# Sheet_TX.net
KiCad netlist of a schematic drawn in Altium Designer
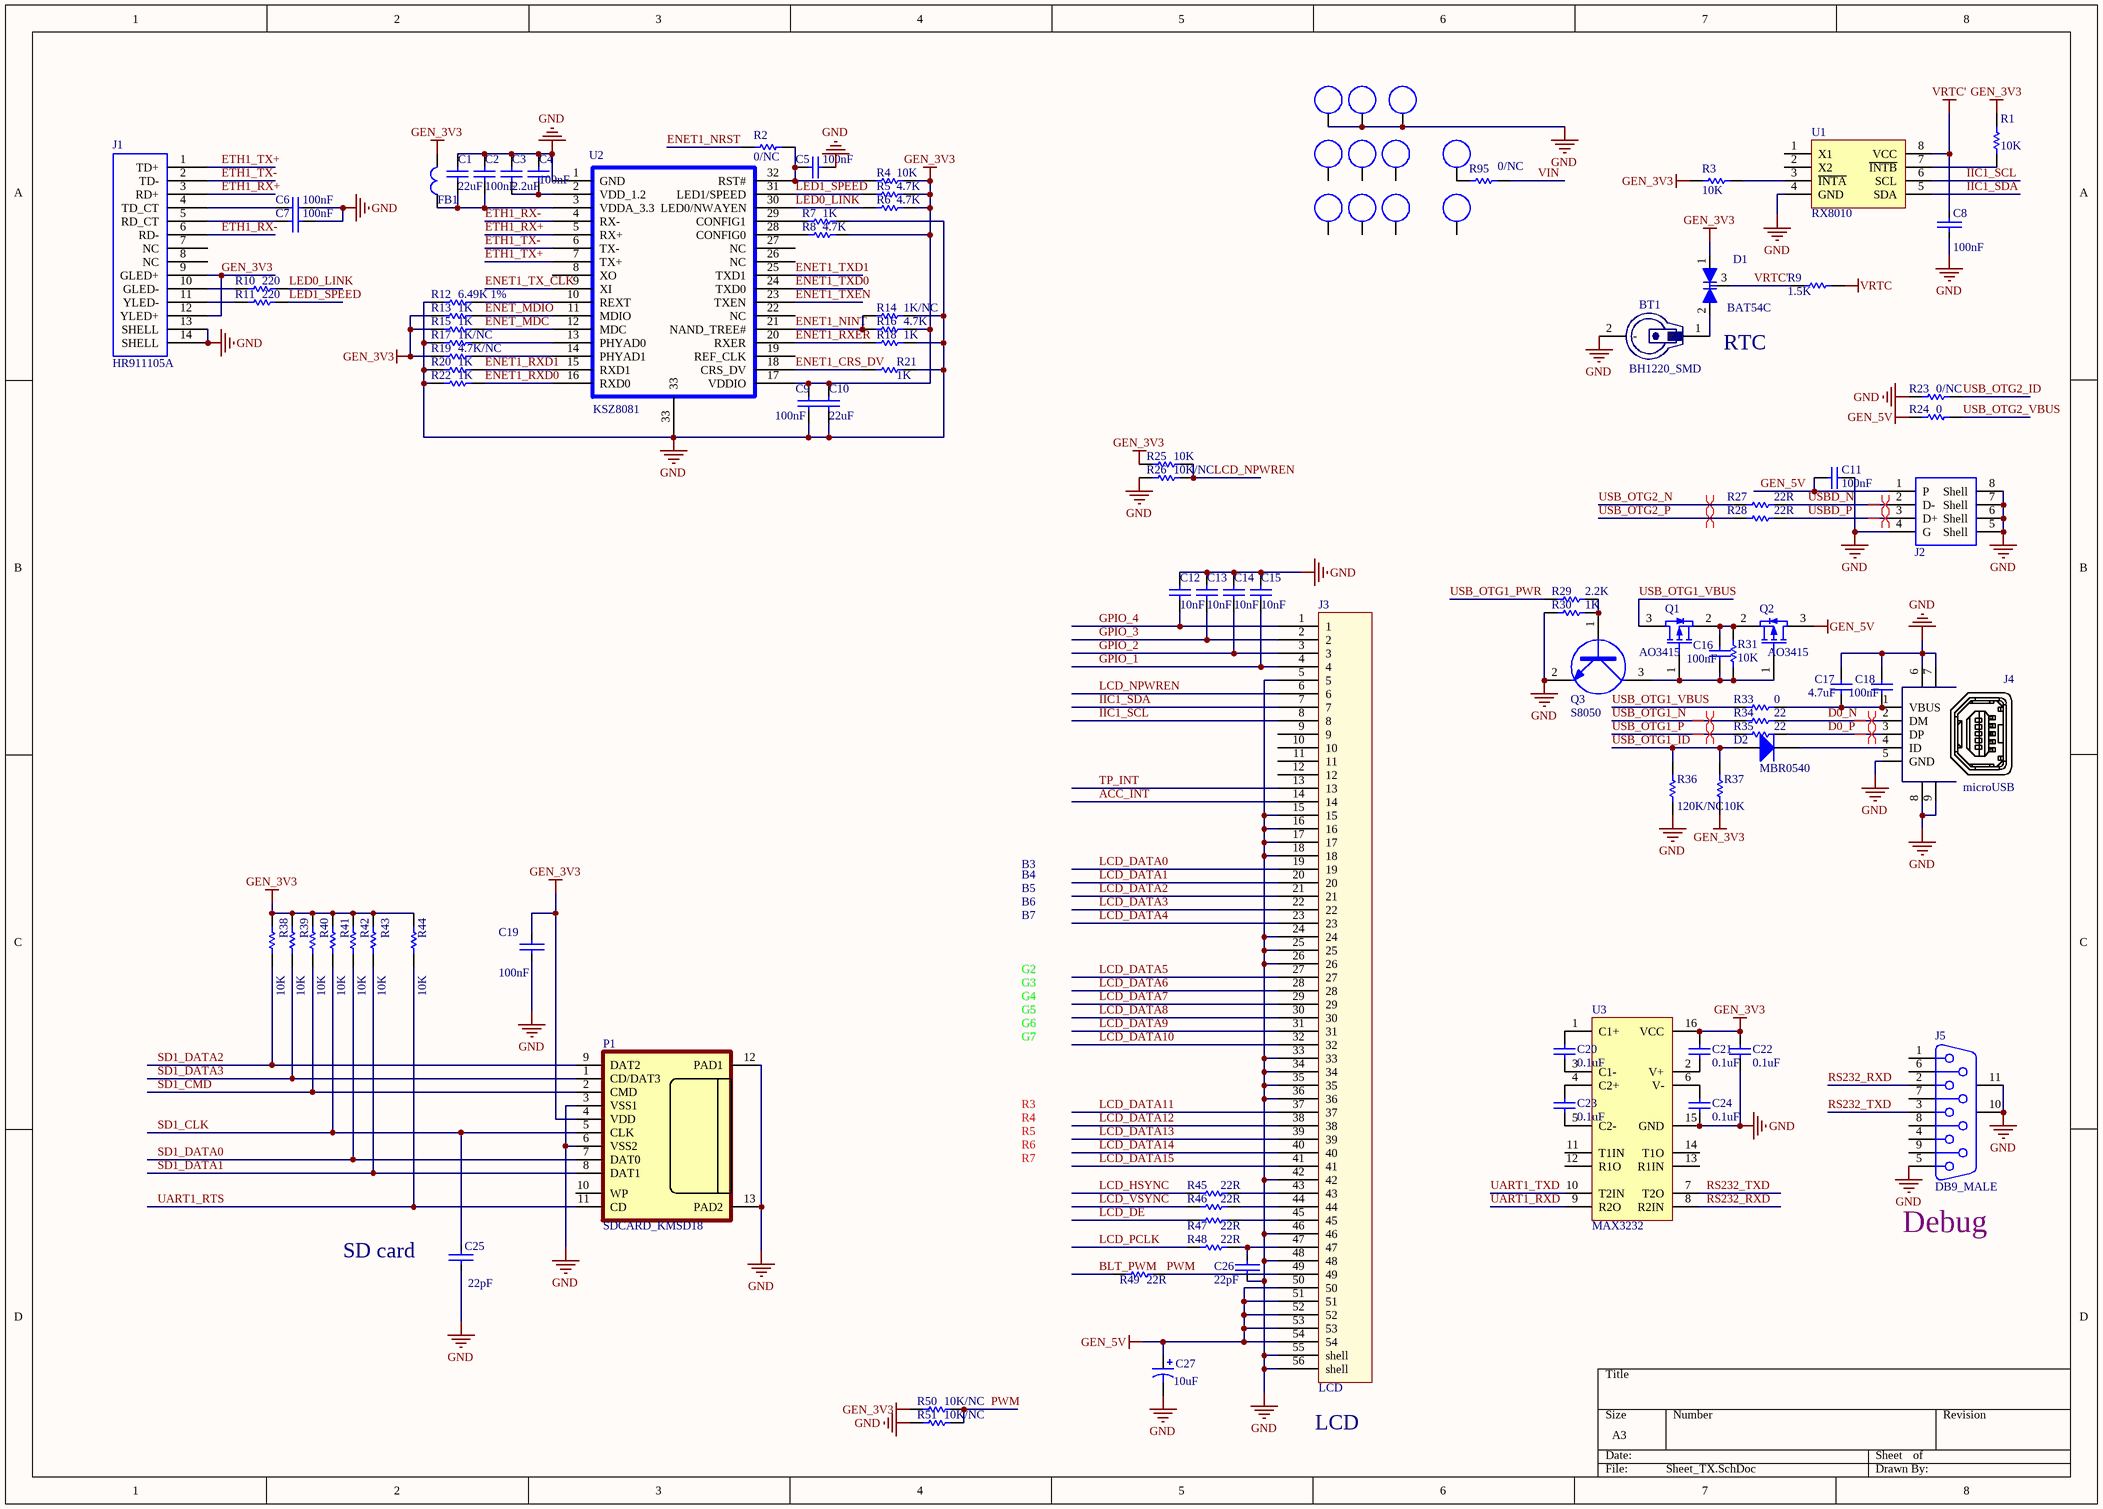
[diagram p0: Sheet_TX.SchDoc]

(export (version "E")
  (design (tool "Eeschema 10.0.6"))
  (components
    (comp (ref "BT1")
      (value "BH1220_SMD")
      (footprint "B1220")
      (libsource (lib "AM335X_bottom") (part "Battery"))
    )
    (comp (ref "C1")
      (value "22uF")
      (footprint "0603")
      (description "Capacitor")
      (fields (field (name "Comment") "Cap") (field (name "PUBLISHER") "Altium Limited"))
      (libsource (lib "Miscellaneous Devices") (part "Cap"))
    )
    (comp (ref "C2")
      (value "100nF")
      (footprint "0603")
      (description "Capacitor")
      (fields (field (name "Comment") "Cap") (field (name "PUBLISHER") "Altium Limited"))
      (libsource (lib "Miscellaneous Devices") (part "Cap"))
    )
    (comp (ref "C3")
      (value "2.2uF")
      (footprint "0603")
      (description "Capacitor")
      (fields (field (name "Comment") "Cap") (field (name "PUBLISHER") "Altium Limited"))
      (libsource (lib "Miscellaneous Devices") (part "Cap"))
    )
    (comp (ref "C4")
      (value "100nF")
      (footprint "0603")
      (description "Capacitor")
      (fields (field (name "Comment") "Cap") (field (name "PUBLISHER") "Altium Limited"))
      (libsource (lib "Miscellaneous Devices") (part "Cap"))
    )
    (comp (ref "C5")
      (value "100nF")
      (footprint "0603")
      (description "Capacitor")
      (fields (field (name "Comment") "Cap") (field (name "PUBLISHER") "Altium Limited"))
      (libsource (lib "Miscellaneous Devices") (part "Cap"))
    )
    (comp (ref "C6")
      (value "100nF")
      (footprint "0603")
      (description "Capacitor")
      (fields (field (name "Comment") "Cap") (field (name "PUBLISHER") "Altium Limited"))
      (libsource (lib "Miscellaneous Devices") (part "Cap"))
    )
    (comp (ref "C7")
      (value "100nF")
      (footprint "0603")
      (description "Capacitor")
      (fields (field (name "Comment") "Cap") (field (name "PUBLISHER") "Altium Limited"))
      (libsource (lib "Miscellaneous Devices") (part "Cap"))
    )
    (comp (ref "C8")
      (value "100nF")
      (footprint "0603")
      (libsource (lib "SMARTCORTEX M3-1700_1") (part "CAP_1"))
    )
    (comp (ref "C9")
      (value "100nF")
      (footprint "0603")
      (description "Capacitor")
      (fields (field (name "Comment") "Cap") (field (name "PUBLISHER") "Altium Limited"))
      (libsource (lib "Miscellaneous Devices") (part "Cap"))
    )
    (comp (ref "C10")
      (value "22uF")
      (footprint "0603")
      (description "Capacitor")
      (fields (field (name "Comment") "Cap") (field (name "PUBLISHER") "Altium Limited"))
      (libsource (lib "Miscellaneous Devices") (part "Cap"))
    )
    (comp (ref "C11")
      (value "100nF")
      (footprint "0603")
      (description "Capacitor (Semiconductor SIM Model)")
      (fields (field (name "Comment") "C0603") (field (name "PUBLISHER") "Altium Limited"))
      (libsource (lib "Miscellaneous Devices") (part "Cap Semi"))
    )
    (comp (ref "C12")
      (value "10nF")
      (footprint "0603")
      (description "Capacitor (Semiconductor SIM Model)")
      (fields (field (name "Comment") "C0603") (field (name "PUBLISHER") "Altium Limited"))
      (libsource (lib "Miscellaneous Devices") (part "Cap Semi"))
    )
    (comp (ref "C13")
      (value "10nF")
      (footprint "0603")
      (description "Capacitor (Semiconductor SIM Model)")
      (fields (field (name "Comment") "C0603") (field (name "PUBLISHER") "Altium Limited"))
      (libsource (lib "Miscellaneous Devices") (part "Cap Semi"))
    )
    (comp (ref "C14")
      (value "10nF")
      (footprint "0603")
      (description "Capacitor (Semiconductor SIM Model)")
      (fields (field (name "Comment") "C0603") (field (name "PUBLISHER") "Altium Limited"))
      (libsource (lib "Miscellaneous Devices") (part "Cap Semi"))
    )
    (comp (ref "C15")
      (value "10nF")
      (footprint "0603")
      (description "Capacitor (Semiconductor SIM Model)")
      (fields (field (name "Comment") "C0603") (field (name "PUBLISHER") "Altium Limited"))
      (libsource (lib "Miscellaneous Devices") (part "Cap Semi"))
    )
    (comp (ref "C16")
      (value "100nF")
      (footprint "0603")
      (description "Capacitor (Semiconductor SIM Model)")
      (fields (field (name "Comment") "C0603") (field (name "PUBLISHER") "Altium Limited"))
      (libsource (lib "Miscellaneous Devices") (part "Cap Semi"))
    )
    (comp (ref "C17")
      (value "4.7uF")
      (footprint "0603")
      (description "Capacitor (Semiconductor SIM Model)")
      (fields (field (name "Comment") "C0603") (field (name "PUBLISHER") "Altium Limited"))
      (libsource (lib "Miscellaneous Devices") (part "Cap Semi"))
    )
    (comp (ref "C18")
      (value "100nF")
      (footprint "0603")
      (description "Capacitor (Semiconductor SIM Model)")
      (fields (field (name "Comment") "C0603") (field (name "PUBLISHER") "Altium Limited"))
      (libsource (lib "Miscellaneous Devices") (part "Cap Semi"))
    )
    (comp (ref "C19")
      (value "100nF")
      (footprint "0603")
      (libsource (lib "SMARTCORTEX M3-1700_1") (part "CAP_1"))
    )
    (comp (ref "C20")
      (value "0.1uF")
      (footprint "0603")
      (description "Capacitor")
      (fields (field (name "Comment") "C0603") (field (name "PUBLISHER") "Altium Limited"))
      (libsource (lib "Miscellaneous Devices") (part "Cap"))
    )
    (comp (ref "C21")
      (value "0.1uF")
      (footprint "0603")
      (description "Capacitor")
      (fields (field (name "Comment") "C0603") (field (name "PUBLISHER") "Altium Limited"))
      (libsource (lib "Miscellaneous Devices") (part "Cap"))
    )
    (comp (ref "C22")
      (value "0.1uF")
      (footprint "0603")
      (description "Capacitor")
      (fields (field (name "Comment") "C0603") (field (name "PUBLISHER") "Altium Limited"))
      (libsource (lib "Miscellaneous Devices") (part "Cap"))
    )
    (comp (ref "C23")
      (value "0.1uF")
      (footprint "0603")
      (description "Capacitor")
      (fields (field (name "Comment") "C0603") (field (name "PUBLISHER") "Altium Limited"))
      (libsource (lib "Miscellaneous Devices") (part "Cap"))
    )
    (comp (ref "C24")
      (value "0.1uF")
      (footprint "0603")
      (description "Capacitor")
      (fields (field (name "Comment") "C0603") (field (name "PUBLISHER") "Altium Limited"))
      (libsource (lib "Miscellaneous Devices") (part "Cap"))
    )
    (comp (ref "C25")
      (value "22pF")
      (footprint "0603")
      (libsource (lib "SMARTCORTEX M3-1700_1") (part "CAP_1"))
    )
    (comp (ref "C26")
      (value "22pF")
      (footprint "0603")
      (libsource (lib "SMARTCORTEX M3-1700_1") (part "CAP_1"))
    )
    (comp (ref "C27")
      (value "10uF")
      (footprint "3216A")
      (description "Polarized Capacitor (Radial)")
      (fields (field (name "Comment") "Cap Pol1") (field (name "PUBLISHER") "Altium Limited"))
      (libsource (lib "Miscellaneous Devices") (part "Cap Pol1"))
    )
    (comp (ref "D1")
      (value "BAT54C")
      (footprint "SOT23")
      (description "SOT23-3_D")
      (libsource (lib "S5PV210_core") (part "BAT54C"))
    )
    (comp (ref "D2")
      (value "MBR0540")
      (footprint "SOD-123")
      (description "Default Diode")
      (fields (field (name "PUBLISHER") "Altium Limited"))
      (libsource (lib "Miscellaneous Devices") (part "Diode"))
    )
    (comp (ref "FB1")
      (value "CZ")
      (footprint "0603")
      (description "Inductor")
      (fields (field (name "PUBLISHER") "Altium Limited"))
      (libsource (lib "Schlib_UL") (part "CZ"))
    )
    (comp (ref "H1") (value "hole") (footprint "HOLE") (libsource (lib "arm_SL") (part "hole")))
    (comp (ref "H2") (value "hole") (footprint "HOLE") (libsource (lib "arm_SL") (part "hole")))
    (comp (ref "H3") (value "hole") (footprint "HOLE") (libsource (lib "arm_SL") (part "hole")))
    (comp (ref "H4") (value "hole") (footprint "HOLE") (libsource (lib "arm_SL") (part "hole")))
    (comp (ref "H7") (value "hole") (footprint "FLQRS") (libsource (lib "arm_SL") (part "hole")))
    (comp (ref "J1")
      (value "HR911105A")
      (footprint "RJ-45A12")
      (libsource (lib "Schlib_UL") (part "HR911105A"))
    )
    (comp (ref "J2") (value "USB-A-F-W") (footprint "USB-C") (libsource (lib "Schlib_YX") (part "USB-A-F-W")))
    (comp (ref "J3") (value "LCD") (footprint "FPC54_A") (libsource (lib "OK6410_LIB") (part "FPC54")))
    (comp (ref "J4")
      (value "microUSB")
      (footprint "MICRO_USB")
      (libsource (lib "AM335X_bottom") (part "miniUSB"))
    )
    (comp (ref "J5")
      (value "DB9_MALE")
      (footprint "DB9R/M")
      (description "Receptacle Assembly, 9 Position, Right Angle")
      (fields (field (name "PUBLISHER") "Altium Limited"))
      (libsource (lib "Miscellaneous Connectors") (part "D Connector 9"))
    )
    (comp (ref "M1") (value "hole") (footprint "mark") (libsource (lib "arm_SL") (part "hole")))
    (comp (ref "M2") (value "hole") (footprint "mark") (libsource (lib "arm_SL") (part "hole")))
    (comp (ref "M3") (value "hole") (footprint "mark") (libsource (lib "arm_SL") (part "hole")))
    (comp (ref "M4") (value "hole") (footprint "mark") (libsource (lib "arm_SL") (part "hole")))
    (comp (ref "M5") (value "hole") (footprint "mark") (libsource (lib "arm_SL") (part "hole")))
    (comp (ref "M6") (value "hole") (footprint "mark") (libsource (lib "arm_SL") (part "hole")))
    (comp (ref "P1")
      (value "SDCARD_KMSD18")
      (footprint "SD-CARD3")
      (libsource (lib "AM335X_bottom") (part "SDCARD_KMSD18"))
    )
    (comp (ref "Q1")
      (value "AO3415")
      (footprint "SOT23")
      (description "P-Channel MOSFET")
      (fields (field (name "PUBLISHER") "Altium Limited"))
      (libsource (lib "Schlib1") (part "MOSFET-P_1"))
    )
    (comp (ref "Q2")
      (value "AO3415")
      (footprint "SOT23")
      (description "P-Channel MOSFET")
      (fields (field (name "PUBLISHER") "Altium Limited"))
      (libsource (lib "Schlib1") (part "MOSFET-P_1"))
    )
    (comp (ref "Q3")
      (value "S8050")
      (footprint "SOT23")
      (description "NPN Transistor")
      (libsource (lib "Schlib_YX") (part "NPN"))
    )
    (comp (ref "R1")
      (value "10K")
      (footprint "0603")
      (description "R0603")
      (fields (field (name "PUBLISHER") "Altium Limited"))
      (libsource (lib "Miscellaneous Devices") (part "Res1"))
    )
    (comp (ref "R2")
      (value "0/NC")
      (footprint "0603")
      (description "Resistor")
      (fields (field (name "Comment") "Res1") (field (name "PUBLISHER") "Altium Limited"))
      (libsource (lib "Miscellaneous Devices") (part "Res1"))
    )
    (comp (ref "R3")
      (value "10K")
      (footprint "0603")
      (description "R0603")
      (fields (field (name "PUBLISHER") "Altium Limited"))
      (libsource (lib "Miscellaneous Devices") (part "Res1"))
    )
    (comp (ref "R4")
      (value "10K")
      (footprint "0603")
      (description "Resistor")
      (fields (field (name "Comment") "Res1") (field (name "PUBLISHER") "Altium Limited"))
      (libsource (lib "Miscellaneous Devices") (part "Res1"))
    )
    (comp (ref "R5")
      (value "4.7K")
      (footprint "0603")
      (description "Resistor")
      (fields (field (name "Comment") "Res1") (field (name "PUBLISHER") "Altium Limited"))
      (libsource (lib "Miscellaneous Devices") (part "Res1"))
    )
    (comp (ref "R6")
      (value "4.7K")
      (footprint "0603")
      (description "Resistor")
      (fields (field (name "Comment") "Res1") (field (name "PUBLISHER") "Altium Limited"))
      (libsource (lib "Miscellaneous Devices") (part "Res1"))
    )
    (comp (ref "R7")
      (value "1K")
      (footprint "0603")
      (description "Resistor")
      (fields (field (name "Comment") "Res1") (field (name "PUBLISHER") "Altium Limited"))
      (libsource (lib "Miscellaneous Devices") (part "Res1"))
    )
    (comp (ref "R8")
      (value "4.7K")
      (footprint "0603")
      (description "Resistor")
      (fields (field (name "Comment") "Res1") (field (name "PUBLISHER") "Altium Limited"))
      (libsource (lib "Miscellaneous Devices") (part "Res1"))
    )
    (comp (ref "R9")
      (value "1.5K")
      (footprint "0603")
      (description "R0603")
      (fields (field (name "Comment") "2.2K") (field (name "PUBLISHER") "Altium Limited"))
      (libsource (lib "Miscellaneous Devices") (part "Res1"))
    )
    (comp (ref "R10")
      (value "220")
      (footprint "0603")
      (description "Resistor")
      (fields (field (name "Comment") "Res1") (field (name "PUBLISHER") "Altium Limited"))
      (libsource (lib "Miscellaneous Devices") (part "Res1"))
    )
    (comp (ref "R11")
      (value "220")
      (footprint "0603")
      (description "Resistor")
      (fields (field (name "Comment") "Res1") (field (name "PUBLISHER") "Altium Limited"))
      (libsource (lib "Miscellaneous Devices") (part "Res1"))
    )
    (comp (ref "R12")
      (value "6.49K 1%")
      (footprint "0603")
      (description "Resistor")
      (fields (field (name "Comment") "Res1") (field (name "PUBLISHER") "Altium Limited"))
      (libsource (lib "Miscellaneous Devices") (part "Res1"))
    )
    (comp (ref "R13")
      (value "1K")
      (footprint "0603")
      (description "Resistor")
      (fields (field (name "Comment") "Res1") (field (name "PUBLISHER") "Altium Limited"))
      (libsource (lib "Miscellaneous Devices") (part "Res1"))
    )
    (comp (ref "R14")
      (value "1K/NC")
      (footprint "0603")
      (description "Resistor")
      (fields (field (name "Comment") "Res1") (field (name "PUBLISHER") "Altium Limited"))
      (libsource (lib "Miscellaneous Devices") (part "Res1"))
    )
    (comp (ref "R15")
      (value "1K")
      (footprint "0603")
      (description "Resistor")
      (fields (field (name "Comment") "Res1") (field (name "PUBLISHER") "Altium Limited"))
      (libsource (lib "Miscellaneous Devices") (part "Res1"))
    )
    (comp (ref "R16")
      (value "4.7K")
      (footprint "0603")
      (description "Resistor")
      (fields (field (name "Comment") "Res1") (field (name "PUBLISHER") "Altium Limited"))
      (libsource (lib "Miscellaneous Devices") (part "Res1"))
    )
    (comp (ref "R17")
      (value "1K/NC")
      (footprint "0603")
      (description "Resistor")
      (fields (field (name "Comment") "Res1") (field (name "PUBLISHER") "Altium Limited"))
      (libsource (lib "Miscellaneous Devices") (part "Res1"))
    )
    (comp (ref "R18")
      (value "1K")
      (footprint "0603")
      (description "Resistor")
      (fields (field (name "Comment") "Res1") (field (name "PUBLISHER") "Altium Limited"))
      (libsource (lib "Miscellaneous Devices") (part "Res1"))
    )
    (comp (ref "R19")
      (value "4.7K/NC")
      (footprint "0603")
      (description "Resistor")
      (fields (field (name "Comment") "Res1") (field (name "PUBLISHER") "Altium Limited"))
      (libsource (lib "Miscellaneous Devices") (part "Res1"))
    )
    (comp (ref "R20")
      (value "1K")
      (footprint "0603")
      (description "Resistor")
      (fields (field (name "Comment") "Res1") (field (name "PUBLISHER") "Altium Limited"))
      (libsource (lib "Miscellaneous Devices") (part "Res1"))
    )
    (comp (ref "R21")
      (value "1K")
      (footprint "0603")
      (description "Resistor")
      (fields (field (name "Comment") "Res1") (field (name "PUBLISHER") "Altium Limited"))
      (libsource (lib "Miscellaneous Devices") (part "Res1"))
    )
    (comp (ref "R22")
      (value "1K")
      (footprint "0603")
      (description "Resistor")
      (fields (field (name "Comment") "Res1") (field (name "PUBLISHER") "Altium Limited"))
      (libsource (lib "Miscellaneous Devices") (part "Res1"))
    )
    (comp (ref "R23")
      (value "0/NC")
      (footprint "0603")
      (description "Resistor")
      (fields (field (name "Comment") "Res1") (field (name "PUBLISHER") "Altium Limited"))
      (libsource (lib "Miscellaneous Devices") (part "Res1"))
    )
    (comp (ref "R24")
      (value "0")
      (footprint "0603")
      (description "Resistor")
      (fields (field (name "Comment") "Res1") (field (name "PUBLISHER") "Altium Limited"))
      (libsource (lib "Miscellaneous Devices") (part "Res1"))
    )
    (comp (ref "R25")
      (value "10K")
      (footprint "0603")
      (description "R0603")
      (fields (field (name "PUBLISHER") "Altium Limited"))
      (libsource (lib "Miscellaneous Devices") (part "Res1"))
    )
    (comp (ref "R26")
      (value "10K/NC")
      (footprint "0603")
      (description "R0603")
      (fields (field (name "Comment") "10K") (field (name "PUBLISHER") "Altium Limited"))
      (libsource (lib "Miscellaneous Devices") (part "Res1"))
    )
    (comp (ref "R27")
      (value "22R")
      (footprint "0603")
      (description "R0603")
      (fields (field (name "Comment") "0R") (field (name "PUBLISHER") "Altium Limited"))
      (libsource (lib "Miscellaneous Devices") (part "Res1"))
    )
    (comp (ref "R28")
      (value "22R")
      (footprint "0603")
      (description "R0603")
      (fields (field (name "Comment") "0R") (field (name "PUBLISHER") "Altium Limited"))
      (libsource (lib "Miscellaneous Devices") (part "Res1"))
    )
    (comp (ref "R29")
      (value "2.2K")
      (footprint "0603")
      (description "Resistor")
      (fields (field (name "Comment") "Res1") (field (name "PUBLISHER") "Altium Limited"))
      (libsource (lib "Miscellaneous Devices") (part "Res1"))
    )
    (comp (ref "R30")
      (value "1K")
      (footprint "0603")
      (description "Resistor")
      (fields (field (name "Comment") "Res1") (field (name "PUBLISHER") "Altium Limited"))
      (libsource (lib "Miscellaneous Devices") (part "Res1"))
    )
    (comp (ref "R31")
      (value "10K")
      (footprint "0603")
      (description "Resistor")
      (fields (field (name "Comment") "Res1") (field (name "PUBLISHER") "Altium Limited"))
      (libsource (lib "Miscellaneous Devices") (part "Res1"))
    )
    (comp (ref "R33")
      (value "0")
      (footprint "0603")
      (description "Resistor")
      (fields (field (name "Comment") "Res1") (field (name "PUBLISHER") "Altium Limited"))
      (libsource (lib "Miscellaneous Devices") (part "Res1"))
    )
    (comp (ref "R34")
      (value "22")
      (footprint "0603")
      (description "R0603")
      (fields (field (name "Comment") "22R") (field (name "PUBLISHER") "Altium Limited"))
      (libsource (lib "Miscellaneous Devices") (part "Res1"))
    )
    (comp (ref "R35")
      (value "22")
      (footprint "0603")
      (description "R0603")
      (fields (field (name "Comment") "22R") (field (name "PUBLISHER") "Altium Limited"))
      (libsource (lib "Miscellaneous Devices") (part "Res1"))
    )
    (comp (ref "R36")
      (value "120K/NC")
      (footprint "0603")
      (description "R0603")
      (fields (field (name "Comment") "120K") (field (name "PUBLISHER") "Altium Limited"))
      (libsource (lib "Miscellaneous Devices") (part "Res1"))
    )
    (comp (ref "R37")
      (value "10K")
      (footprint "0603")
      (description "R0603")
      (fields (field (name "PUBLISHER") "Altium Limited"))
      (libsource (lib "Miscellaneous Devices") (part "Res1"))
    )
    (comp (ref "R38")
      (value "10K")
      (footprint "0603")
      (description "R0603")
      (fields (field (name "PUBLISHER") "Altium Limited"))
      (libsource (lib "Miscellaneous Devices") (part "Res1"))
    )
    (comp (ref "R39")
      (value "10K")
      (footprint "0603")
      (description "R0603")
      (fields (field (name "PUBLISHER") "Altium Limited"))
      (libsource (lib "Miscellaneous Devices") (part "Res1"))
    )
    (comp (ref "R40")
      (value "10K")
      (footprint "0603")
      (description "R0603")
      (fields (field (name "PUBLISHER") "Altium Limited"))
      (libsource (lib "Miscellaneous Devices") (part "Res1"))
    )
    (comp (ref "R41")
      (value "10K")
      (footprint "0603")
      (description "R0603")
      (fields (field (name "PUBLISHER") "Altium Limited"))
      (libsource (lib "Miscellaneous Devices") (part "Res1"))
    )
    (comp (ref "R42")
      (value "10K")
      (footprint "0603")
      (description "R0603")
      (fields (field (name "PUBLISHER") "Altium Limited"))
      (libsource (lib "Miscellaneous Devices") (part "Res1"))
    )
    (comp (ref "R43")
      (value "10K")
      (footprint "0603")
      (description "R0603")
      (fields (field (name "PUBLISHER") "Altium Limited"))
      (libsource (lib "Miscellaneous Devices") (part "Res1"))
    )
    (comp (ref "R44")
      (value "10K")
      (footprint "0603")
      (description "R0603")
      (fields (field (name "PUBLISHER") "Altium Limited"))
      (libsource (lib "Miscellaneous Devices") (part "Res1"))
    )
    (comp (ref "R45")
      (value "22R")
      (footprint "0603")
      (description "R0603")
      (fields (field (name "PUBLISHER") "Altium Limited"))
      (libsource (lib "Miscellaneous Devices") (part "Res1"))
    )
    (comp (ref "R46")
      (value "22R")
      (footprint "0603")
      (description "R0603")
      (fields (field (name "PUBLISHER") "Altium Limited"))
      (libsource (lib "Miscellaneous Devices") (part "Res1"))
    )
    (comp (ref "R47")
      (value "22R")
      (footprint "0603")
      (description "R0603")
      (fields (field (name "PUBLISHER") "Altium Limited"))
      (libsource (lib "Miscellaneous Devices") (part "Res1"))
    )
    (comp (ref "R48")
      (value "22R")
      (footprint "0603")
      (description "R0603")
      (fields (field (name "PUBLISHER") "Altium Limited"))
      (libsource (lib "Miscellaneous Devices") (part "Res1"))
    )
    (comp (ref "R49")
      (value "22R")
      (footprint "0603")
      (description "R0603")
      (fields (field (name "PUBLISHER") "Altium Limited"))
      (libsource (lib "Miscellaneous Devices") (part "Res1"))
    )
    (comp (ref "R50")
      (value "10K/NC")
      (footprint "0603")
      (description "R0603")
      (fields (field (name "Comment") "10K") (field (name "PUBLISHER") "Altium Limited"))
      (libsource (lib "Miscellaneous Devices") (part "Res1"))
    )
    (comp (ref "R51")
      (value "10K/NC")
      (footprint "0603")
      (description "R0603")
      (fields (field (name "Comment") "10K") (field (name "PUBLISHER") "Altium Limited"))
      (libsource (lib "Miscellaneous Devices") (part "Res1"))
    )
    (comp (ref "R95")
      (value "0/NC")
      (footprint "0805")
      (description "R0603")
      (fields (field (name "Comment") "10K") (field (name "PUBLISHER") "Altium Limited"))
      (libsource (lib "Miscellaneous Devices") (part "Res1"))
    )
    (comp (ref "U1") (value "RX8010") (footprint "SOIC-8N") (libsource (lib "AM335X_bottom") (part "DS1337")))
    (comp (ref "U2") (value "KSZ8081") (footprint "QFN-32") (libsource (lib "Schlib_UL") (part "KSZ8081RNB")))
    (comp (ref "U3")
      (value "MAX3232")
      (footprint "SO-16")
      (description "TI SOIC16")
      (libsource (lib "Schlib_210") (part "MAX202E"))
    )
  )
  (nets
    (net (code "1") (name "/ACC_INT") (class "Default")
      (node (ref "J3") (pin "14") (pinfunction "14_14") (pintype "passive"))
    )
    (net (code "2") (name "/BLT_PWM") (class "Default")
      (node (ref "R49") (pin "1") (pinfunction "1_1") (pintype "passive"))
    )
    (net (code "3") (name "/D0_N") (class "Default")
      (node (ref "J4") (pin "2") (pinfunction "DM_2") (pintype "passive"))
      (node (ref "R34") (pin "2") (pinfunction "2_2") (pintype "passive"))
    )
    (net (code "4") (name "/D0_P") (class "Default")
      (node (ref "J4") (pin "3") (pinfunction "DP_3") (pintype "passive"))
      (node (ref "R35") (pin "2") (pinfunction "2_2") (pintype "passive"))
    )
    (net (code "5") (name "/ENET1_CRS_DV") (class "Default")
      (node (ref "R21") (pin "2") (pinfunction "2_2") (pintype "passive"))
      (node (ref "U2") (pin "18") (pinfunction "CRS_DV_18") (pintype "passive"))
    )
    (net (code "6") (name "/ENET1_NINT") (class "Default")
      (node (ref "R14") (pin "2") (pinfunction "2_2") (pintype "passive"))
      (node (ref "R16") (pin "2") (pinfunction "2_2") (pintype "passive"))
      (node (ref "U2") (pin "21") (pinfunction "NAND_TREE#_21") (pintype "passive"))
    )
    (net (code "7") (name "/ENET1_NRST") (class "Default")
      (node (ref "R2") (pin "1") (pinfunction "1_1") (pintype "passive"))
    )
    (net (code "8") (name "/ENET1_RXD0") (class "Default")
      (node (ref "R22") (pin "1") (pinfunction "1_1") (pintype "passive"))
      (node (ref "U2") (pin "16") (pinfunction "RXD0_16") (pintype "passive"))
    )
    (net (code "9") (name "/ENET1_RXD1") (class "Default")
      (node (ref "R20") (pin "1") (pinfunction "1_1") (pintype "passive"))
      (node (ref "U2") (pin "15") (pinfunction "RXD1_15") (pintype "passive"))
    )
    (net (code "10") (name "/ENET1_RXER") (class "Default")
      (node (ref "R18") (pin "2") (pinfunction "2_2") (pintype "passive"))
      (node (ref "U2") (pin "20") (pinfunction "RXER_20") (pintype "passive"))
    )
    (net (code "11") (name "/ENET1_TXD0") (class "Default")
      (node (ref "U2") (pin "24") (pinfunction "TXD0_24") (pintype "passive"))
    )
    (net (code "12") (name "/ENET1_TXD1") (class "Default")
      (node (ref "U2") (pin "25") (pinfunction "TXD1_25") (pintype "passive"))
    )
    (net (code "13") (name "/ENET1_TXEN") (class "Default")
      (node (ref "U2") (pin "23") (pinfunction "TXEN_23") (pintype "passive"))
    )
    (net (code "14") (name "/ENET1_TX_CLK") (class "Default")
      (node (ref "U2") (pin "9") (pinfunction "XI_9") (pintype "passive"))
    )
    (net (code "15") (name "/ENET_MDC") (class "Default")
      (node (ref "R15") (pin "1") (pinfunction "1_1") (pintype "passive"))
      (node (ref "U2") (pin "12") (pinfunction "MDC_12") (pintype "passive"))
    )
    (net (code "16") (name "/ENET_MDIO") (class "Default")
      (node (ref "R13") (pin "1") (pinfunction "1_1") (pintype "passive"))
      (node (ref "U2") (pin "11") (pinfunction "MDIO_11") (pintype "passive"))
    )
    (net (code "17") (name "/ETH1_RX+") (class "Default")
      (node (ref "J1") (pin "3") (pinfunction "RD+_3") (pintype "passive"))
      (node (ref "U2") (pin "5") (pinfunction "RX+_5") (pintype "passive"))
    )
    (net (code "18") (name "/ETH1_RX-") (class "Default")
      (node (ref "J1") (pin "6") (pinfunction "RD-_6") (pintype "passive"))
      (node (ref "U2") (pin "4") (pinfunction "RX-_4") (pintype "passive"))
    )
    (net (code "19") (name "/ETH1_TX+") (class "Default")
      (node (ref "J1") (pin "1") (pinfunction "TD+_1") (pintype "passive"))
      (node (ref "U2") (pin "7") (pinfunction "TX+_7") (pintype "passive"))
    )
    (net (code "20") (name "/ETH1_TX-") (class "Default")
      (node (ref "J1") (pin "2") (pinfunction "TD-_2") (pintype "passive"))
      (node (ref "U2") (pin "6") (pinfunction "TX-_6") (pintype "passive"))
    )
    (net (code "21") (name "/GPIO_1") (class "Default")
      (node (ref "C15") (pin "2") (pinfunction "2_2") (pintype "passive"))
      (node (ref "J3") (pin "4") (pinfunction "4_4") (pintype "passive"))
    )
    (net (code "22") (name "/GPIO_2") (class "Default")
      (node (ref "C14") (pin "2") (pinfunction "2_2") (pintype "passive"))
      (node (ref "J3") (pin "3") (pinfunction "3_3") (pintype "passive"))
    )
    (net (code "23") (name "/GPIO_3") (class "Default")
      (node (ref "C13") (pin "2") (pinfunction "2_2") (pintype "passive"))
      (node (ref "J3") (pin "2") (pinfunction "2_2") (pintype "passive"))
    )
    (net (code "24") (name "/GPIO_4") (class "Default")
      (node (ref "C12") (pin "2") (pinfunction "2_2") (pintype "passive"))
      (node (ref "J3") (pin "1") (pinfunction "1_1") (pintype "passive"))
    )
    (net (code "25") (name "/IIC1_SCL") (class "Default")
      (node (ref "J3") (pin "8") (pinfunction "8_8") (pintype "passive"))
      (node (ref "U1") (pin "6") (pinfunction "SCL_6") (pintype "passive"))
    )
    (net (code "26") (name "/IIC1_SDA") (class "Default")
      (node (ref "J3") (pin "7") (pinfunction "7_7") (pintype "passive"))
      (node (ref "U1") (pin "5") (pinfunction "SDA_5") (pintype "passive"))
    )
    (net (code "27") (name "/LCD_DATA0") (class "Default")
      (node (ref "J3") (pin "19") (pinfunction "19_19") (pintype "passive"))
    )
    (net (code "28") (name "/LCD_DATA1") (class "Default")
      (node (ref "J3") (pin "20") (pinfunction "20_20") (pintype "passive"))
    )
    (net (code "29") (name "/LCD_DATA2") (class "Default")
      (node (ref "J3") (pin "21") (pinfunction "21_21") (pintype "passive"))
    )
    (net (code "30") (name "/LCD_DATA3") (class "Default")
      (node (ref "J3") (pin "22") (pinfunction "22_22") (pintype "passive"))
    )
    (net (code "31") (name "/LCD_DATA4") (class "Default")
      (node (ref "J3") (pin "23") (pinfunction "23_23") (pintype "passive"))
    )
    (net (code "32") (name "/LCD_DATA5") (class "Default")
      (node (ref "J3") (pin "27") (pinfunction "27_27") (pintype "passive"))
    )
    (net (code "33") (name "/LCD_DATA6") (class "Default")
      (node (ref "J3") (pin "28") (pinfunction "28_28") (pintype "passive"))
    )
    (net (code "34") (name "/LCD_DATA7") (class "Default")
      (node (ref "J3") (pin "29") (pinfunction "29_29") (pintype "passive"))
    )
    (net (code "35") (name "/LCD_DATA8") (class "Default")
      (node (ref "J3") (pin "30") (pinfunction "30_30") (pintype "passive"))
    )
    (net (code "36") (name "/LCD_DATA9") (class "Default")
      (node (ref "J3") (pin "31") (pinfunction "31_31") (pintype "passive"))
    )
    (net (code "37") (name "/LCD_DATA10") (class "Default")
      (node (ref "J3") (pin "32") (pinfunction "32_32") (pintype "passive"))
    )
    (net (code "38") (name "/LCD_DATA11") (class "Default")
      (node (ref "J3") (pin "37") (pinfunction "37_37") (pintype "passive"))
    )
    (net (code "39") (name "/LCD_DATA12") (class "Default")
      (node (ref "J3") (pin "38") (pinfunction "38_38") (pintype "passive"))
    )
    (net (code "40") (name "/LCD_DATA13") (class "Default")
      (node (ref "J3") (pin "39") (pinfunction "39_39") (pintype "passive"))
    )
    (net (code "41") (name "/LCD_DATA14") (class "Default")
      (node (ref "J3") (pin "40") (pinfunction "40_40") (pintype "passive"))
    )
    (net (code "42") (name "/LCD_DATA15") (class "Default")
      (node (ref "J3") (pin "41") (pinfunction "41_41") (pintype "passive"))
    )
    (net (code "43") (name "/LCD_DE") (class "Default")
      (node (ref "R47") (pin "1") (pinfunction "1_1") (pintype "passive"))
    )
    (net (code "44") (name "/LCD_HSYNC") (class "Default")
      (node (ref "R45") (pin "1") (pinfunction "1_1") (pintype "passive"))
    )
    (net (code "45") (name "/LCD_NPWREN") (class "Default")
      (node (ref "J3") (pin "6") (pinfunction "6_6") (pintype "passive"))
      (node (ref "R25") (pin "2") (pinfunction "2_2") (pintype "passive"))
      (node (ref "R26") (pin "2") (pinfunction "2_2") (pintype "passive"))
    )
    (net (code "46") (name "/LCD_PCLK") (class "Default")
      (node (ref "R48") (pin "1") (pinfunction "1_1") (pintype "passive"))
    )
    (net (code "47") (name "/LCD_VSYNC") (class "Default")
      (node (ref "R46") (pin "1") (pinfunction "1_1") (pintype "passive"))
    )
    (net (code "48") (name "/LED0_LINK") (class "Default")
      (node (ref "R10") (pin "1") (pinfunction "1_1") (pintype "passive"))
      (node (ref "R6") (pin "2") (pinfunction "2_2") (pintype "passive"))
      (node (ref "U2") (pin "30") (pinfunction "LED0/NWAYEN_30") (pintype "passive"))
    )
    (net (code "49") (name "/LED1_SPEED") (class "Default")
      (node (ref "R11") (pin "1") (pinfunction "1_1") (pintype "passive"))
      (node (ref "R5") (pin "2") (pinfunction "2_2") (pintype "passive"))
      (node (ref "U2") (pin "31") (pinfunction "LED1/SPEED_31") (pintype "passive"))
    )
    (net (code "50") (name "/PWM") (class "Default")
      (node (ref "J3") (pin "49") (pinfunction "49_49") (pintype "passive"))
      (node (ref "R49") (pin "2") (pinfunction "2_2") (pintype "passive"))
      (node (ref "R50") (pin "2") (pinfunction "2_2") (pintype "passive"))
      (node (ref "R51") (pin "2") (pinfunction "2_2") (pintype "passive"))
    )
    (net (code "51") (name "/RS232_RXD") (class "Default")
      (node (ref "J5") (pin "2") (pinfunction "2_2") (pintype "passive"))
      (node (ref "U3") (pin "8") (pinfunction "R2IN_8") (pintype "passive"))
    )
    (net (code "52") (name "/RS232_TXD") (class "Default")
      (node (ref "J5") (pin "3") (pinfunction "3_3") (pintype "passive"))
      (node (ref "U3") (pin "7") (pinfunction "T2O_7") (pintype "passive"))
    )
    (net (code "53") (name "/SD1_CLK") (class "Default")
      (node (ref "C25") (pin "1") (pintype "passive"))
      (node (ref "P1") (pin "5") (pinfunction "CLK_5") (pintype "passive"))
      (node (ref "R41") (pin "2") (pinfunction "2_2") (pintype "passive"))
    )
    (net (code "54") (name "/SD1_CMD") (class "Default")
      (node (ref "P1") (pin "2") (pinfunction "CMD_2") (pintype "passive"))
      (node (ref "R40") (pin "2") (pinfunction "2_2") (pintype "passive"))
    )
    (net (code "55") (name "/SD1_DATA0") (class "Default")
      (node (ref "P1") (pin "7") (pinfunction "DAT0_7") (pintype "passive"))
      (node (ref "R42") (pin "2") (pinfunction "2_2") (pintype "passive"))
    )
    (net (code "56") (name "/SD1_DATA1") (class "Default")
      (node (ref "P1") (pin "8") (pinfunction "DAT1_8") (pintype "passive"))
      (node (ref "R43") (pin "2") (pinfunction "2_2") (pintype "passive"))
    )
    (net (code "57") (name "/SD1_DATA2") (class "Default")
      (node (ref "P1") (pin "9") (pinfunction "DAT2_9") (pintype "passive"))
      (node (ref "R38") (pin "2") (pinfunction "2_2") (pintype "passive"))
    )
    (net (code "58") (name "/SD1_DATA3") (class "Default")
      (node (ref "P1") (pin "1") (pinfunction "CD/DAT3_1") (pintype "passive"))
      (node (ref "R39") (pin "2") (pinfunction "2_2") (pintype "passive"))
    )
    (net (code "59") (name "/TP_INT") (class "Default")
      (node (ref "J3") (pin "13") (pinfunction "13_13") (pintype "passive"))
    )
    (net (code "60") (name "/UART1_RTS") (class "Default")
      (node (ref "P1") (pin "11") (pinfunction "CD_11") (pintype "passive"))
      (node (ref "R44") (pin "2") (pinfunction "2_2") (pintype "passive"))
    )
    (net (code "61") (name "/UART1_RXD") (class "Default")
      (node (ref "U3") (pin "9") (pinfunction "R2O_9") (pintype "passive"))
    )
    (net (code "62") (name "/UART1_TXD") (class "Default")
      (node (ref "U3") (pin "10") (pinfunction "T2IN_10") (pintype "passive"))
    )
    (net (code "63") (name "/USBD_N") (class "Default")
      (node (ref "J2") (pin "2") (pinfunction "D-_2") (pintype "passive"))
      (node (ref "R27") (pin "2") (pinfunction "2_2") (pintype "passive"))
    )
    (net (code "64") (name "/USBD_P") (class "Default")
      (node (ref "J2") (pin "3") (pinfunction "D+_3") (pintype "passive"))
      (node (ref "R28") (pin "2") (pinfunction "2_2") (pintype "passive"))
    )
    (net (code "65") (name "/USB_OTG1_ID") (class "Default")
      (node (ref "D2") (pin "1") (pinfunction "A_1") (pintype "passive"))
      (node (ref "R36") (pin "2") (pinfunction "2_2") (pintype "passive"))
      (node (ref "R37") (pin "2") (pinfunction "2_2") (pintype "passive"))
    )
    (net (code "66") (name "/USB_OTG1_N") (class "Default")
      (node (ref "R34") (pin "1") (pinfunction "1_1") (pintype "passive"))
    )
    (net (code "67") (name "/USB_OTG1_P") (class "Default")
      (node (ref "R35") (pin "1") (pinfunction "1_1") (pintype "passive"))
    )
    (net (code "68") (name "/USB_OTG1_PWR") (class "Default")
      (node (ref "R29") (pin "2") (pinfunction "2_2") (pintype "passive"))
    )
    (net (code "69") (name "/USB_OTG1_VBUS") (class "Default")
      (node (ref "Q1") (pin "3") (pinfunction "D_3") (pintype "passive"))
      (node (ref "R33") (pin "1") (pinfunction "1_1") (pintype "passive"))
    )
    (net (code "70") (name "/USB_OTG2_ID") (class "Default")
      (node (ref "R23") (pin "2") (pinfunction "2_2") (pintype "passive"))
    )
    (net (code "71") (name "/USB_OTG2_N") (class "Default")
      (node (ref "R27") (pin "1") (pinfunction "1_1") (pintype "passive"))
    )
    (net (code "72") (name "/USB_OTG2_P") (class "Default")
      (node (ref "R28") (pin "1") (pinfunction "1_1") (pintype "passive"))
    )
    (net (code "73") (name "/USB_OTG2_VBUS") (class "Default")
      (node (ref "R24") (pin "2") (pinfunction "2_2") (pintype "passive"))
    )
    (net (code "74") (name "/VIN") (class "Default")
      (node (ref "R95") (pin "2") (pinfunction "2_2") (pintype "passive"))
    )
    (net (code "75") (name "GEN_3V3") (class "Default")
      (node (ref "C10") (pin "1") (pinfunction "1_1") (pintype "passive"))
      (node (ref "C19") (pin "1") (pintype "passive"))
      (node (ref "C21") (pin "1") (pinfunction "1_1") (pintype "passive"))
      (node (ref "C22") (pin "1") (pinfunction "1_1") (pintype "passive"))
      (node (ref "C9") (pin "1") (pinfunction "1_1") (pintype "passive"))
      (node (ref "D1") (pin "1") (pinfunction "1_1") (pintype "passive"))
      (node (ref "FB1") (pin "2") (pinfunction "2_2") (pintype "passive"))
      (node (ref "J1") (pin "12") (pinfunction "YLED+_12") (pintype "passive"))
      (node (ref "J1") (pin "9") (pinfunction "GLED+_9") (pintype "passive"))
      (node (ref "P1") (pin "4") (pinfunction "VDD_4") (pintype "passive"))
      (node (ref "R1") (pin "1") (pinfunction "1_1") (pintype "passive"))
      (node (ref "R13") (pin "2") (pinfunction "2_2") (pintype "passive"))
      (node (ref "R15") (pin "2") (pinfunction "2_2") (pintype "passive"))
      (node (ref "R16") (pin "1") (pinfunction "1_1") (pintype "passive"))
      (node (ref "R19") (pin "2") (pinfunction "2_2") (pintype "passive"))
      (node (ref "R25") (pin "1") (pinfunction "1_1") (pintype "passive"))
      (node (ref "R3") (pin "1") (pinfunction "1_1") (pintype "passive"))
      (node (ref "R37") (pin "1") (pinfunction "1_1") (pintype "passive"))
      (node (ref "R38") (pin "1") (pinfunction "1_1") (pintype "passive"))
      (node (ref "R39") (pin "1") (pinfunction "1_1") (pintype "passive"))
      (node (ref "R4") (pin "1") (pinfunction "1_1") (pintype "passive"))
      (node (ref "R40") (pin "1") (pinfunction "1_1") (pintype "passive"))
      (node (ref "R41") (pin "1") (pinfunction "1_1") (pintype "passive"))
      (node (ref "R42") (pin "1") (pinfunction "1_1") (pintype "passive"))
      (node (ref "R43") (pin "1") (pinfunction "1_1") (pintype "passive"))
      (node (ref "R44") (pin "1") (pinfunction "1_1") (pintype "passive"))
      (node (ref "R5") (pin "1") (pinfunction "1_1") (pintype "passive"))
      (node (ref "R50") (pin "1") (pinfunction "1_1") (pintype "passive"))
      (node (ref "R6") (pin "1") (pinfunction "1_1") (pintype "passive"))
      (node (ref "R8") (pin "1") (pinfunction "1_1") (pintype "passive"))
      (node (ref "U2") (pin "17") (pinfunction "VDDIO_17") (pintype "passive"))
      (node (ref "U3") (pin "16") (pinfunction "VCC_16") (pintype "passive"))
    )
    (net (code "76") (name "GEN_5V") (class "Default")
      (node (ref "C11") (pin "2") (pinfunction "2_2") (pintype "passive"))
      (node (ref "C27") (pin "1") (pinfunction "1_1") (pintype "passive"))
      (node (ref "J2") (pin "1") (pinfunction "P_1") (pintype "passive"))
      (node (ref "J3") (pin "50") (pinfunction "50_50") (pintype "passive"))
      (node (ref "J3") (pin "51") (pinfunction "51_51") (pintype "passive"))
      (node (ref "J3") (pin "52") (pinfunction "52_52") (pintype "passive"))
      (node (ref "J3") (pin "53") (pinfunction "53_53") (pintype "passive"))
      (node (ref "J3") (pin "54") (pinfunction "54_54") (pintype "passive"))
      (node (ref "Q2") (pin "3") (pinfunction "D_3") (pintype "passive"))
      (node (ref "R24") (pin "1") (pinfunction "1_1") (pintype "passive"))
    )
    (net (code "77") (name "GND") (class "Default")
      (node (ref "BT1") (pin "2") (pinfunction "-_2") (pintype "passive"))
      (node (ref "C1") (pin "1") (pinfunction "1_1") (pintype "passive"))
      (node (ref "C10") (pin "2") (pinfunction "2_2") (pintype "passive"))
      (node (ref "C11") (pin "1") (pinfunction "1_1") (pintype "passive"))
      (node (ref "C12") (pin "1") (pinfunction "1_1") (pintype "passive"))
      (node (ref "C13") (pin "1") (pinfunction "1_1") (pintype "passive"))
      (node (ref "C14") (pin "1") (pinfunction "1_1") (pintype "passive"))
      (node (ref "C15") (pin "1") (pinfunction "1_1") (pintype "passive"))
      (node (ref "C17") (pin "1") (pinfunction "1_1") (pintype "passive"))
      (node (ref "C18") (pin "1") (pinfunction "1_1") (pintype "passive"))
      (node (ref "C19") (pin "2") (pintype "passive"))
      (node (ref "C2") (pin "1") (pinfunction "1_1") (pintype "passive"))
      (node (ref "C22") (pin "2") (pinfunction "2_2") (pintype "passive"))
      (node (ref "C24") (pin "2") (pinfunction "2_2") (pintype "passive"))
      (node (ref "C25") (pin "2") (pintype "passive"))
      (node (ref "C26") (pin "2") (pintype "passive"))
      (node (ref "C27") (pin "2") (pinfunction "2_2") (pintype "passive"))
      (node (ref "C3") (pin "1") (pinfunction "1_1") (pintype "passive"))
      (node (ref "C4") (pin "1") (pinfunction "1_1") (pintype "passive"))
      (node (ref "C5") (pin "1") (pinfunction "1_1") (pintype "passive"))
      (node (ref "C6") (pin "1") (pinfunction "1_1") (pintype "passive"))
      (node (ref "C7") (pin "1") (pinfunction "1_1") (pintype "passive"))
      (node (ref "C8") (pin "2") (pintype "passive"))
      (node (ref "C9") (pin "2") (pinfunction "2_2") (pintype "passive"))
      (node (ref "H1") (pin "1") (pinfunction "1_1") (pintype "passive"))
      (node (ref "H2") (pin "1") (pinfunction "1_1") (pintype "passive"))
      (node (ref "H4") (pin "1") (pinfunction "1_1") (pintype "passive"))
      (node (ref "J1") (pin "13") (pinfunction "SHELL_13") (pintype "passive"))
      (node (ref "J1") (pin "14") (pinfunction "SHELL_14") (pintype "passive"))
      (node (ref "J2") (pin "4") (pinfunction "G_4") (pintype "passive"))
      (node (ref "J2") (pin "5") (pinfunction "Shell_5") (pintype "passive"))
      (node (ref "J2") (pin "6") (pinfunction "Shell_6") (pintype "passive"))
      (node (ref "J2") (pin "7") (pinfunction "Shell_7") (pintype "power_in"))
      (node (ref "J2") (pin "8") (pinfunction "Shell_8") (pintype "power_in"))
      (node (ref "J3") (pin "15") (pinfunction "15_15") (pintype "passive"))
      (node (ref "J3") (pin "16") (pinfunction "16_16") (pintype "passive"))
      (node (ref "J3") (pin "17") (pinfunction "17_17") (pintype "passive"))
      (node (ref "J3") (pin "18") (pinfunction "18_18") (pintype "passive"))
      (node (ref "J3") (pin "24") (pinfunction "24_24") (pintype "passive"))
      (node (ref "J3") (pin "25") (pinfunction "25_25") (pintype "passive"))
      (node (ref "J3") (pin "26") (pinfunction "26_26") (pintype "passive"))
      (node (ref "J3") (pin "33") (pinfunction "33_33") (pintype "passive"))
      (node (ref "J3") (pin "34") (pinfunction "34_34") (pintype "passive"))
      (node (ref "J3") (pin "35") (pinfunction "35_35") (pintype "passive"))
      (node (ref "J3") (pin "36") (pinfunction "36_36") (pintype "passive"))
      (node (ref "J3") (pin "42") (pinfunction "42_42") (pintype "passive"))
      (node (ref "J3") (pin "46") (pinfunction "46_46") (pintype "passive"))
      (node (ref "J3") (pin "48") (pinfunction "48_48") (pintype "passive"))
      (node (ref "J3") (pin "5") (pinfunction "5_5") (pintype "passive"))
      (node (ref "J3") (pin "55") (pinfunction "shell_55") (pintype "passive"))
      (node (ref "J3") (pin "56") (pinfunction "shell_56") (pintype "passive"))
      (node (ref "J4") (pin "5") (pinfunction "GND_5") (pintype "passive"))
      (node (ref "J4") (pin "6") (pinfunction "6_6") (pintype "passive"))
      (node (ref "J4") (pin "7") (pinfunction "7_7") (pintype "passive"))
      (node (ref "J4") (pin "8") (pinfunction "8_8") (pintype "passive"))
      (node (ref "J4") (pin "9") (pinfunction "9_9") (pintype "passive"))
      (node (ref "J5") (pin "10") (pinfunction "MH1_10") (pintype "passive"))
      (node (ref "J5") (pin "11") (pinfunction "MH2_11") (pintype "passive"))
      (node (ref "J5") (pin "5") (pinfunction "5_5") (pintype "passive"))
      (node (ref "P1") (pin "12") (pinfunction "PAD1_12") (pintype "passive"))
      (node (ref "P1") (pin "13") (pinfunction "PAD2_13") (pintype "passive"))
      (node (ref "P1") (pin "3") (pinfunction "VSS1_3") (pintype "passive"))
      (node (ref "P1") (pin "6") (pinfunction "VSS2_6") (pintype "passive"))
      (node (ref "Q3") (pin "2") (pinfunction "E_2") (pintype "passive"))
      (node (ref "R12") (pin "2") (pinfunction "2_2") (pintype "passive"))
      (node (ref "R14") (pin "1") (pinfunction "1_1") (pintype "passive"))
      (node (ref "R17") (pin "2") (pinfunction "2_2") (pintype "passive"))
      (node (ref "R18") (pin "1") (pinfunction "1_1") (pintype "passive"))
      (node (ref "R20") (pin "2") (pinfunction "2_2") (pintype "passive"))
      (node (ref "R21") (pin "1") (pinfunction "1_1") (pintype "passive"))
      (node (ref "R22") (pin "2") (pinfunction "2_2") (pintype "passive"))
      (node (ref "R23") (pin "1") (pinfunction "1_1") (pintype "passive"))
      (node (ref "R26") (pin "1") (pinfunction "1_1") (pintype "passive"))
      (node (ref "R30") (pin "2") (pinfunction "2_2") (pintype "passive"))
      (node (ref "R36") (pin "1") (pinfunction "1_1") (pintype "passive"))
      (node (ref "R51") (pin "1") (pinfunction "1_1") (pintype "passive"))
      (node (ref "R7") (pin "1") (pinfunction "1_1") (pintype "passive"))
      (node (ref "U1") (pin "4") (pinfunction "GND_4") (pintype "passive"))
      (node (ref "U2") (pin "1") (pinfunction "GND_1") (pintype "passive"))
      (node (ref "U2") (pin "33") (pinfunction "33_33") (pintype "passive"))
      (node (ref "U3") (pin "15") (pinfunction "GND_15") (pintype "passive"))
    )
    (net (code "78") (name "Net-(BT1-+)") (class "Default")
      (node (ref "BT1") (pin "1") (pinfunction "+_1") (pintype "passive"))
      (node (ref "D1") (pin "2") (pinfunction "2_2") (pintype "passive"))
    )
    (net (code "79") (name "Net-(C26-Pad1)") (class "Default")
      (node (ref "C26") (pin "1") (pintype "passive"))
      (node (ref "J3") (pin "47") (pinfunction "47_47") (pintype "passive"))
      (node (ref "R48") (pin "2") (pinfunction "2_2") (pintype "passive"))
    )
    (net (code "80") (name "Net-(D2-K)") (class "Default")
      (node (ref "D2") (pin "2") (pinfunction "K_2") (pintype "passive"))
      (node (ref "J4") (pin "4") (pinfunction "ID_4") (pintype "passive"))
    )
    (net (code "81") (name "Net-(H3-Pad1)") (class "Default")
      (node (ref "H3") (pin "1") (pinfunction "1_1") (pintype "passive"))
      (node (ref "R95") (pin "1") (pinfunction "1_1") (pintype "passive"))
    )
    (net (code "82") (name "Net-(J1-GLED-)") (class "Default")
      (node (ref "J1") (pin "10") (pinfunction "GLED-_10") (pintype "passive"))
      (node (ref "R10") (pin "2") (pinfunction "2_2") (pintype "passive"))
    )
    (net (code "83") (name "Net-(J1-RD_CT)") (class "Default")
      (node (ref "C7") (pin "2") (pinfunction "2_2") (pintype "passive"))
      (node (ref "J1") (pin "5") (pinfunction "RD_CT_5") (pintype "passive"))
    )
    (net (code "84") (name "Net-(J1-TD_CT)") (class "Default")
      (node (ref "C6") (pin "2") (pinfunction "2_2") (pintype "passive"))
      (node (ref "J1") (pin "4") (pinfunction "TD_CT_4") (pintype "passive"))
    )
    (net (code "85") (name "Net-(J1-YLED-)") (class "Default")
      (node (ref "J1") (pin "11") (pinfunction "YLED-_11") (pintype "passive"))
      (node (ref "R11") (pin "2") (pinfunction "2_2") (pintype "passive"))
    )
    (net (code "86") (name "Net-(J3-Pad43)") (class "Default")
      (node (ref "J3") (pin "43") (pinfunction "43_43") (pintype "passive"))
      (node (ref "R45") (pin "2") (pinfunction "2_2") (pintype "passive"))
    )
    (net (code "87") (name "Net-(J3-Pad44)") (class "Default")
      (node (ref "J3") (pin "44") (pinfunction "44_44") (pintype "passive"))
      (node (ref "R46") (pin "2") (pinfunction "2_2") (pintype "passive"))
    )
    (net (code "88") (name "Net-(J3-Pad45)") (class "Default")
      (node (ref "J3") (pin "45") (pinfunction "45_45") (pintype "passive"))
      (node (ref "R47") (pin "2") (pinfunction "2_2") (pintype "passive"))
    )
    (net (code "89") (name "Net-(J4-VBUS)") (class "Default")
      (node (ref "C17") (pin "2") (pinfunction "2_2") (pintype "passive"))
      (node (ref "C18") (pin "2") (pinfunction "2_2") (pintype "passive"))
      (node (ref "J4") (pin "1") (pinfunction "VBUS_1") (pintype "passive"))
      (node (ref "R33") (pin "2") (pinfunction "2_2") (pintype "passive"))
    )
    (net (code "90") (name "Net-(Q1-G)") (class "Default")
      (node (ref "C16") (pin "2") (pinfunction "2_2") (pintype "passive"))
      (node (ref "Q1") (pin "1") (pinfunction "G_1") (pintype "passive"))
      (node (ref "Q2") (pin "1") (pinfunction "G_1") (pintype "passive"))
      (node (ref "Q3") (pin "3") (pinfunction "C_3") (pintype "passive"))
      (node (ref "R31") (pin "1") (pinfunction "1_1") (pintype "passive"))
    )
    (net (code "91") (name "Net-(Q1-S)") (class "Default")
      (node (ref "C16") (pin "1") (pinfunction "1_1") (pintype "passive"))
      (node (ref "Q1") (pin "2") (pinfunction "S_2") (pintype "passive"))
      (node (ref "Q2") (pin "2") (pinfunction "S_2") (pintype "passive"))
      (node (ref "R31") (pin "2") (pinfunction "2_2") (pintype "passive"))
    )
    (net (code "92") (name "Net-(Q3-B)") (class "Default")
      (node (ref "Q3") (pin "1") (pinfunction "B_1") (pintype "passive"))
      (node (ref "R29") (pin "1") (pinfunction "1_1") (pintype "passive"))
      (node (ref "R30") (pin "1") (pinfunction "1_1") (pintype "passive"))
    )
    (net (code "93") (name "Net-(U1-~{INTA})") (class "Default")
      (node (ref "R3") (pin "2") (pinfunction "2_2") (pintype "passive"))
      (node (ref "U1") (pin "3") (pinfunction "~{INTA}_3") (pintype "passive"))
    )
    (net (code "94") (name "Net-(U1-~{INTB})") (class "Default")
      (node (ref "R1") (pin "2") (pinfunction "2_2") (pintype "passive"))
      (node (ref "U1") (pin "7") (pinfunction "~{INTB}_7") (pintype "passive"))
    )
    (net (code "95") (name "Net-(U2-CONFIG0)") (class "Default")
      (node (ref "R8") (pin "2") (pinfunction "2_2") (pintype "passive"))
      (node (ref "U2") (pin "28") (pinfunction "CONFIG0_28") (pintype "passive"))
    )
    (net (code "96") (name "Net-(U2-CONFIG1)") (class "Default")
      (node (ref "R7") (pin "2") (pinfunction "2_2") (pintype "passive"))
      (node (ref "U2") (pin "29") (pinfunction "CONFIG1_29") (pintype "passive"))
    )
    (net (code "97") (name "Net-(U2-PHYAD0)") (class "Default")
      (node (ref "R17") (pin "1") (pinfunction "1_1") (pintype "passive"))
      (node (ref "U2") (pin "13") (pinfunction "PHYAD0_13") (pintype "passive"))
    )
    (net (code "98") (name "Net-(U2-PHYAD1)") (class "Default")
      (node (ref "R19") (pin "1") (pinfunction "1_1") (pintype "passive"))
      (node (ref "U2") (pin "14") (pinfunction "PHYAD1_14") (pintype "passive"))
    )
    (net (code "99") (name "Net-(U2-REXT)") (class "Default")
      (node (ref "R12") (pin "1") (pinfunction "1_1") (pintype "passive"))
      (node (ref "U2") (pin "10") (pinfunction "REXT_10") (pintype "passive"))
    )
    (net (code "100") (name "Net-(U2-RST#)") (class "Default")
      (node (ref "C5") (pin "2") (pinfunction "2_2") (pintype "passive"))
      (node (ref "R2") (pin "2") (pinfunction "2_2") (pintype "passive"))
      (node (ref "R4") (pin "2") (pinfunction "2_2") (pintype "passive"))
      (node (ref "U2") (pin "32") (pinfunction "RST#_32") (pintype "passive"))
    )
    (net (code "101") (name "Net-(U2-VDDA_3.3)") (class "Default")
      (node (ref "C1") (pin "2") (pinfunction "2_2") (pintype "passive"))
      (node (ref "C2") (pin "2") (pinfunction "2_2") (pintype "passive"))
      (node (ref "FB1") (pin "1") (pinfunction "1_1") (pintype "passive"))
      (node (ref "U2") (pin "3") (pinfunction "VDDA_3.3_3") (pintype "passive"))
    )
    (net (code "102") (name "Net-(U2-VDD_1.2)") (class "Default")
      (node (ref "C3") (pin "2") (pinfunction "2_2") (pintype "passive"))
      (node (ref "C4") (pin "2") (pinfunction "2_2") (pintype "passive"))
      (node (ref "U2") (pin "2") (pinfunction "VDD_1.2_2") (pintype "passive"))
    )
    (net (code "103") (name "Net-(U3-C1+)") (class "Default")
      (node (ref "C20") (pin "1") (pinfunction "1_1") (pintype "passive"))
      (node (ref "U3") (pin "1") (pinfunction "C1+_1") (pintype "passive"))
    )
    (net (code "104") (name "Net-(U3-C1-)") (class "Default")
      (node (ref "C20") (pin "2") (pinfunction "2_2") (pintype "passive"))
      (node (ref "U3") (pin "3") (pinfunction "C1-_3") (pintype "passive"))
    )
    (net (code "105") (name "Net-(U3-C2+)") (class "Default")
      (node (ref "C23") (pin "1") (pinfunction "1_1") (pintype "passive"))
      (node (ref "U3") (pin "4") (pinfunction "C2+_4") (pintype "passive"))
    )
    (net (code "106") (name "Net-(U3-C2-)") (class "Default")
      (node (ref "C23") (pin "2") (pinfunction "2_2") (pintype "passive"))
      (node (ref "U3") (pin "5") (pinfunction "C2-_5") (pintype "passive"))
    )
    (net (code "107") (name "Net-(U3-V+)") (class "Default")
      (node (ref "C21") (pin "2") (pinfunction "2_2") (pintype "passive"))
      (node (ref "U3") (pin "2") (pinfunction "V+_2") (pintype "passive"))
    )
    (net (code "108") (name "Net-(U3-V-)") (class "Default")
      (node (ref "C24") (pin "1") (pinfunction "1_1") (pintype "passive"))
      (node (ref "U3") (pin "6") (pinfunction "V-_6") (pintype "passive"))
    )
    (net (code "109") (name "VRTC") (class "Default")
      (node (ref "R9") (pin "1") (pinfunction "1_1") (pintype "passive"))
    )
    (net (code "110") (name "VRTC'") (class "Default")
      (node (ref "C8") (pin "1") (pintype "passive"))
      (node (ref "D1") (pin "3") (pinfunction "3_3") (pintype "passive"))
      (node (ref "R9") (pin "2") (pinfunction "2_2") (pintype "passive"))
      (node (ref "U1") (pin "8") (pinfunction "VCC_8") (pintype "passive"))
    )
    (net (code "111") (name "unconnected-(H7-Pad1)") (class "Default")
      (node (ref "H7") (pin "1") (pinfunction "1_1") (pintype "passive"))
    )
    (net (code "112") (name "unconnected-(J1-NC-Pad7)") (class "Default")
      (node (ref "J1") (pin "7") (pinfunction "NC_7") (pintype "passive"))
    )
    (net (code "113") (name "unconnected-(J1-NC-Pad8)") (class "Default")
      (node (ref "J1") (pin "8") (pinfunction "NC_8") (pintype "passive"))
    )
    (net (code "114") (name "unconnected-(J3-Pad9)") (class "Default")
      (node (ref "J3") (pin "9") (pinfunction "9_9") (pintype "passive"))
    )
    (net (code "115") (name "unconnected-(J3-Pad10)") (class "Default")
      (node (ref "J3") (pin "10") (pinfunction "10_10") (pintype "passive"))
    )
    (net (code "116") (name "unconnected-(J3-Pad11)") (class "Default")
      (node (ref "J3") (pin "11") (pinfunction "11_11") (pintype "passive"))
    )
    (net (code "117") (name "unconnected-(J3-Pad12)") (class "Default")
      (node (ref "J3") (pin "12") (pinfunction "12_12") (pintype "passive"))
    )
    (net (code "118") (name "unconnected-(J5-Pad1)") (class "Default")
      (node (ref "J5") (pin "1") (pinfunction "1_1") (pintype "passive"))
    )
    (net (code "119") (name "unconnected-(J5-Pad4)") (class "Default")
      (node (ref "J5") (pin "4") (pinfunction "4_4") (pintype "passive"))
    )
    (net (code "120") (name "unconnected-(J5-Pad6)") (class "Default")
      (node (ref "J5") (pin "6") (pinfunction "6_6") (pintype "passive"))
    )
    (net (code "121") (name "unconnected-(J5-Pad7)") (class "Default")
      (node (ref "J5") (pin "7") (pinfunction "7_7") (pintype "passive"))
    )
    (net (code "122") (name "unconnected-(J5-Pad8)") (class "Default")
      (node (ref "J5") (pin "8") (pinfunction "8_8") (pintype "passive"))
    )
    (net (code "123") (name "unconnected-(J5-Pad9)") (class "Default")
      (node (ref "J5") (pin "9") (pinfunction "9_9") (pintype "passive"))
    )
    (net (code "124") (name "unconnected-(M1-Pad1)") (class "Default")
      (node (ref "M1") (pin "1") (pinfunction "1_1") (pintype "passive"))
    )
    (net (code "125") (name "unconnected-(M2-Pad1)") (class "Default")
      (node (ref "M2") (pin "1") (pinfunction "1_1") (pintype "passive"))
    )
    (net (code "126") (name "unconnected-(M3-Pad1)") (class "Default")
      (node (ref "M3") (pin "1") (pinfunction "1_1") (pintype "passive"))
    )
    (net (code "127") (name "unconnected-(M4-Pad1)") (class "Default")
      (node (ref "M4") (pin "1") (pinfunction "1_1") (pintype "passive"))
    )
    (net (code "128") (name "unconnected-(M5-Pad1)") (class "Default")
      (node (ref "M5") (pin "1") (pinfunction "1_1") (pintype "passive"))
    )
    (net (code "129") (name "unconnected-(M6-Pad1)") (class "Default")
      (node (ref "M6") (pin "1") (pinfunction "1_1") (pintype "passive"))
    )
    (net (code "130") (name "unconnected-(P1-WP-Pad10)") (class "Default")
      (node (ref "P1") (pin "10") (pinfunction "WP_10") (pintype "passive"))
    )
    (net (code "131") (name "unconnected-(U1-X1-Pad1)") (class "Default")
      (node (ref "U1") (pin "1") (pinfunction "X1_1") (pintype "passive"))
    )
    (net (code "132") (name "unconnected-(U1-X2-Pad2)") (class "Default")
      (node (ref "U1") (pin "2") (pinfunction "X2_2") (pintype "passive"))
    )
    (net (code "133") (name "unconnected-(U2-NC-Pad22)") (class "Default")
      (node (ref "U2") (pin "22") (pinfunction "NC_22") (pintype "passive"))
    )
    (net (code "134") (name "unconnected-(U2-NC-Pad26)") (class "Default")
      (node (ref "U2") (pin "26") (pinfunction "NC_26") (pintype "passive"))
    )
    (net (code "135") (name "unconnected-(U2-NC-Pad27)") (class "Default")
      (node (ref "U2") (pin "27") (pinfunction "NC_27") (pintype "passive"))
    )
    (net (code "136") (name "unconnected-(U2-REF_CLK-Pad19)") (class "Default")
      (node (ref "U2") (pin "19") (pinfunction "REF_CLK_19") (pintype "passive"))
    )
    (net (code "137") (name "unconnected-(U2-XO-Pad8)") (class "Default")
      (node (ref "U2") (pin "8") (pinfunction "XO_8") (pintype "passive"))
    )
    (net (code "138") (name "unconnected-(U3-R1IN-Pad13)") (class "Default")
      (node (ref "U3") (pin "13") (pinfunction "R1IN_13") (pintype "passive"))
    )
    (net (code "139") (name "unconnected-(U3-R1O-Pad12)") (class "Default")
      (node (ref "U3") (pin "12") (pinfunction "R1O_12") (pintype "passive"))
    )
    (net (code "140") (name "unconnected-(U3-T1IN-Pad11)") (class "Default")
      (node (ref "U3") (pin "11") (pinfunction "T1IN_11") (pintype "passive"))
    )
    (net (code "141") (name "unconnected-(U3-T1O-Pad14)") (class "Default")
      (node (ref "U3") (pin "14") (pinfunction "T1O_14") (pintype "passive"))
    )
  )
)
